# 10_DDR2.net
KiCad netlist of a schematic drawn in Altium Designer
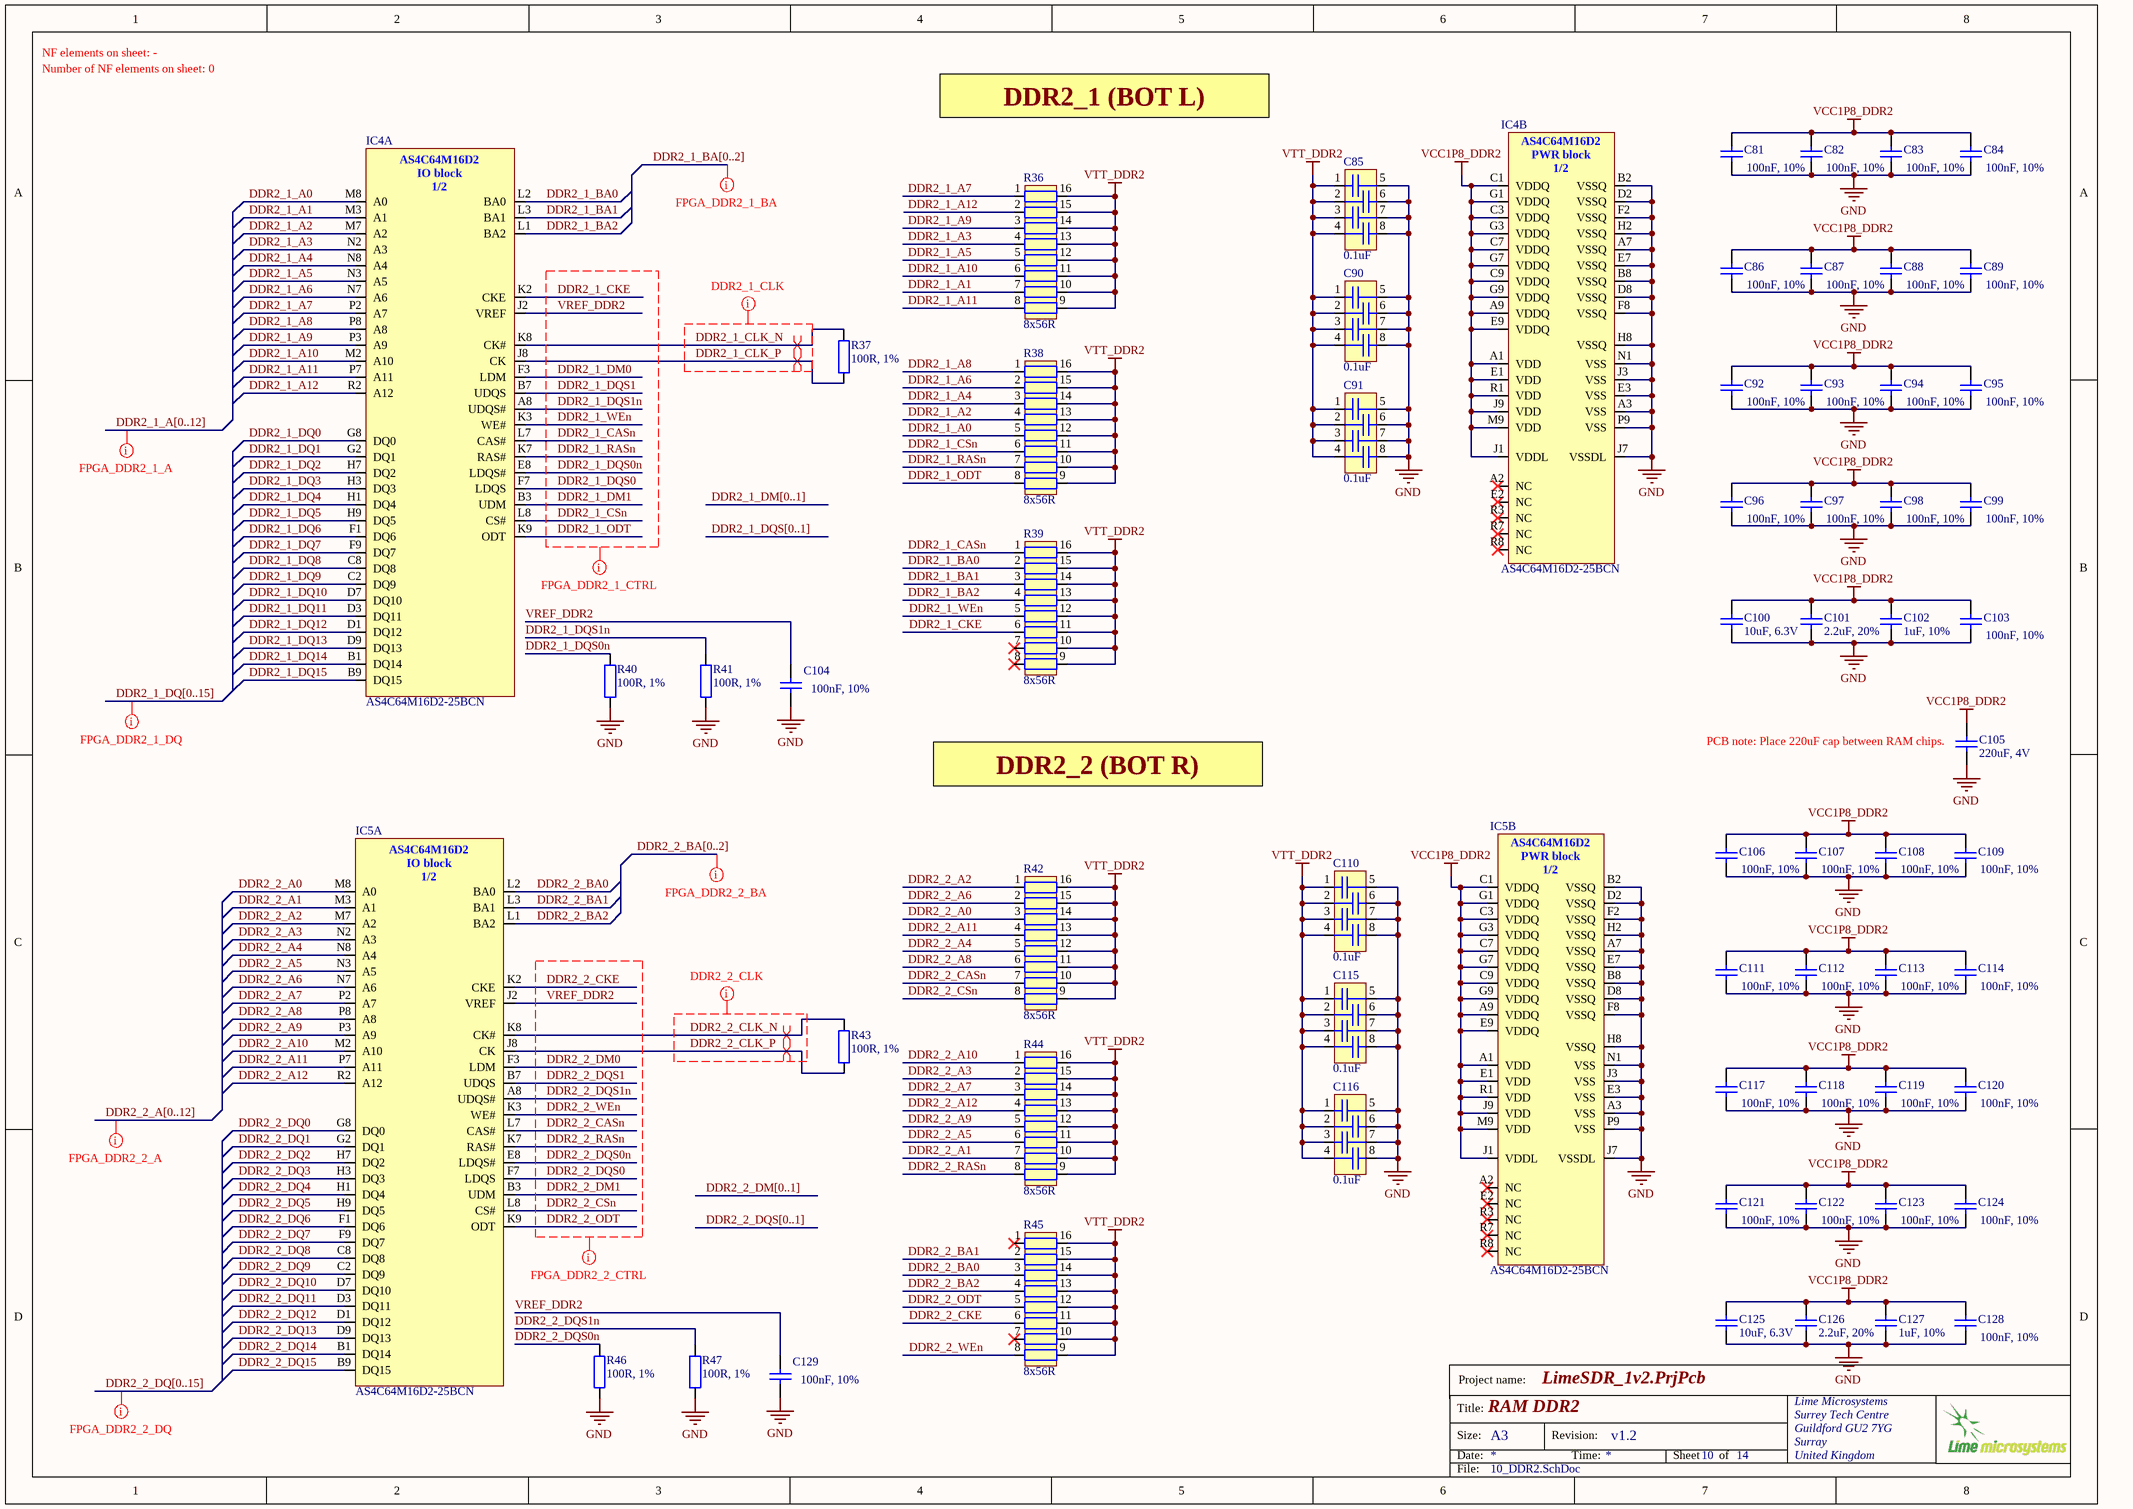
[diagram p0: 10_DDR2.SchDoc]

(export (version "E")
  (design (tool "Eeschema 10.0.6"))
  (components
    (comp (ref "C81")
      (value "100nF, 10%")
      (footprint "CAP0402")
      (fields
        (field (name "TOLERANCE") "10 %")
        (field (name "MANUFACTURER") "Murata Electronics")
        (field (name "MANUFACTURER PART NUMBER") "GRM155R71C104KA88D")
      )
      (libsource (lib "LimeFPGAboard_schLib") (part "Cap_0603"))
    )
    (comp (ref "C82")
      (value "100nF, 10%")
      (footprint "CAP0402")
      (fields
        (field (name "TOLERANCE") "10 %")
        (field (name "MANUFACTURER") "Murata Electronics")
        (field (name "MANUFACTURER PART NUMBER") "GRM155R71C104KA88D")
      )
      (libsource (lib "LimeFPGAboard_schLib") (part "Cap_0603"))
    )
    (comp (ref "C83")
      (value "100nF, 10%")
      (footprint "CAP0402")
      (fields
        (field (name "TOLERANCE") "10 %")
        (field (name "MANUFACTURER") "Murata Electronics")
        (field (name "MANUFACTURER PART NUMBER") "GRM155R71C104KA88D")
      )
      (libsource (lib "LimeFPGAboard_schLib") (part "Cap_0603"))
    )
    (comp (ref "C84")
      (value "100nF, 10%")
      (footprint "CAP0402")
      (fields
        (field (name "TOLERANCE") "10 %")
        (field (name "MANUFACTURER") "Murata Electronics")
        (field (name "MANUFACTURER PART NUMBER") "GRM155R71C104KA88D")
      )
      (libsource (lib "LimeFPGAboard_schLib") (part "Cap_0603"))
    )
    (comp (ref "C85")
      (value "0.1uF")
      (footprint "CKCA43X7R1C104M100AA")
      (fields (field (name "MANUFACTURER") "TDK") (field (name "TOLERANCE") "20 %"))
      (libsource (lib "LimeFPGAboard_schLib") (part "4X_cap_array_1206"))
    )
    (comp (ref "C86")
      (value "100nF, 10%")
      (footprint "CAP0402")
      (fields
        (field (name "TOLERANCE") "10 %")
        (field (name "MANUFACTURER") "Murata Electronics")
        (field (name "MANUFACTURER PART NUMBER") "GRM155R71C104KA88D")
      )
      (libsource (lib "LimeFPGAboard_schLib") (part "Cap_0603"))
    )
    (comp (ref "C87")
      (value "100nF, 10%")
      (footprint "CAP0402")
      (fields
        (field (name "TOLERANCE") "10 %")
        (field (name "MANUFACTURER") "Murata Electronics")
        (field (name "MANUFACTURER PART NUMBER") "GRM155R71C104KA88D")
      )
      (libsource (lib "LimeFPGAboard_schLib") (part "Cap_0603"))
    )
    (comp (ref "C88")
      (value "100nF, 10%")
      (footprint "CAP0402")
      (fields
        (field (name "TOLERANCE") "10 %")
        (field (name "MANUFACTURER") "Murata Electronics")
        (field (name "MANUFACTURER PART NUMBER") "GRM155R71C104KA88D")
      )
      (libsource (lib "LimeFPGAboard_schLib") (part "Cap_0603"))
    )
    (comp (ref "C89")
      (value "100nF, 10%")
      (footprint "CAP0402")
      (fields
        (field (name "TOLERANCE") "10 %")
        (field (name "MANUFACTURER") "Murata Electronics")
        (field (name "MANUFACTURER PART NUMBER") "GRM155R71C104KA88D")
      )
      (libsource (lib "LimeFPGAboard_schLib") (part "Cap_0603"))
    )
    (comp (ref "C90")
      (value "0.1uF")
      (footprint "CKCA43X7R1C104M100AA")
      (fields (field (name "MANUFACTURER") "TDK") (field (name "TOLERANCE") "20 %"))
      (libsource (lib "LimeFPGAboard_schLib") (part "4X_cap_array_1206"))
    )
    (comp (ref "C91")
      (value "0.1uF")
      (footprint "CKCA43X7R1C104M100AA")
      (fields (field (name "MANUFACTURER") "TDK") (field (name "TOLERANCE") "20 %"))
      (libsource (lib "LimeFPGAboard_schLib") (part "4X_cap_array_1206"))
    )
    (comp (ref "C92")
      (value "100nF, 10%")
      (footprint "CAP0402")
      (fields
        (field (name "TOLERANCE") "10 %")
        (field (name "MANUFACTURER") "Murata Electronics")
        (field (name "MANUFACTURER PART NUMBER") "GRM155R71C104KA88D")
      )
      (libsource (lib "LimeFPGAboard_schLib") (part "Cap_0603"))
    )
    (comp (ref "C93")
      (value "100nF, 10%")
      (footprint "CAP0402")
      (fields
        (field (name "TOLERANCE") "10 %")
        (field (name "MANUFACTURER") "Murata Electronics")
        (field (name "MANUFACTURER PART NUMBER") "GRM155R71C104KA88D")
      )
      (libsource (lib "LimeFPGAboard_schLib") (part "Cap_0603"))
    )
    (comp (ref "C94")
      (value "100nF, 10%")
      (footprint "CAP0402")
      (fields
        (field (name "TOLERANCE") "10 %")
        (field (name "MANUFACTURER") "Murata Electronics")
        (field (name "MANUFACTURER PART NUMBER") "GRM155R71C104KA88D")
      )
      (libsource (lib "LimeFPGAboard_schLib") (part "Cap_0603"))
    )
    (comp (ref "C95")
      (value "100nF, 10%")
      (footprint "CAP0402")
      (fields
        (field (name "TOLERANCE") "10 %")
        (field (name "MANUFACTURER") "Murata Electronics")
        (field (name "MANUFACTURER PART NUMBER") "GRM155R71C104KA88D")
      )
      (libsource (lib "LimeFPGAboard_schLib") (part "Cap_0603"))
    )
    (comp (ref "C96")
      (value "100nF, 10%")
      (footprint "CAP0402")
      (fields
        (field (name "TOLERANCE") "10 %")
        (field (name "MANUFACTURER") "Murata Electronics")
        (field (name "MANUFACTURER PART NUMBER") "GRM155R71C104KA88D")
      )
      (libsource (lib "LimeFPGAboard_schLib") (part "Cap_0603"))
    )
    (comp (ref "C97")
      (value "100nF, 10%")
      (footprint "CAP0402")
      (fields
        (field (name "TOLERANCE") "10 %")
        (field (name "MANUFACTURER") "Murata Electronics")
        (field (name "MANUFACTURER PART NUMBER") "GRM155R71C104KA88D")
      )
      (libsource (lib "LimeFPGAboard_schLib") (part "Cap_0603"))
    )
    (comp (ref "C98")
      (value "100nF, 10%")
      (footprint "CAP0402")
      (fields
        (field (name "TOLERANCE") "10 %")
        (field (name "MANUFACTURER") "Murata Electronics")
        (field (name "MANUFACTURER PART NUMBER") "GRM155R71C104KA88D")
      )
      (libsource (lib "LimeFPGAboard_schLib") (part "Cap_0603"))
    )
    (comp (ref "C99")
      (value "100nF, 10%")
      (footprint "CAP0402")
      (fields
        (field (name "TOLERANCE") "10 %")
        (field (name "MANUFACTURER") "Murata Electronics")
        (field (name "MANUFACTURER PART NUMBER") "GRM155R71C104KA88D")
      )
      (libsource (lib "LimeFPGAboard_schLib") (part "Cap_0603"))
    )
    (comp (ref "C100")
      (value "10uF, 6.3V")
      (footprint "CAP0603")
      (fields (field (name "TOLERANCE") "±20%") (field (name "MANUFACTURER") "Yageo"))
      (libsource (lib "LimeFPGAboard_schLib") (part "Cap_0603"))
    )
    (comp (ref "C101")
      (value "2.2uF, 20%")
      (footprint "CAP0402")
      (fields (field (name "MANUFACTURER") "TDK Corporation") (field (name "TOLERANCE") "±20%"))
      (libsource (lib "LimeMicroAltiumLib_schLib") (part "Cap_0402"))
    )
    (comp (ref "C102")
      (value "1uF, 10%")
      (footprint "CAP0402")
      (fields (field (name "MANUFACTURER") "TDK"))
      (libsource (lib "LimeMicroAltiumLib_schLib") (part "Cap_0402"))
    )
    (comp (ref "C103")
      (value "100nF, 10%")
      (footprint "CAP0402")
      (fields
        (field (name "TOLERANCE") "10 %")
        (field (name "MANUFACTURER") "Murata Electronics")
        (field (name "MANUFACTURER PART NUMBER") "GRM155R71C104KA88D")
      )
      (libsource (lib "LimeFPGAboard_schLib") (part "Cap_0603"))
    )
    (comp (ref "C104")
      (value "100nF, 10%")
      (footprint "CAP0402")
      (fields
        (field (name "TOLERANCE") "10 %")
        (field (name "MANUFACTURER") "Murata Electronics")
        (field (name "MANUFACTURER PART NUMBER") "GRM155R71C104KA88D")
      )
      (libsource (lib "LimeFPGAboard_schLib") (part "Cap_0603"))
    )
    (comp (ref "C105")
      (value "220uF, 4V")
      (footprint "LimeMicroAltiumLib_pcbLib:CAP1206")
      (fields
        (field (name "MANUFACTURER PART NUMBER") "GRM31CR60G227ME11L")
        (field (name "MANUFACTURER") "Murata Electronics North America")
        (field (name "TOLERANCE") "±20%")
      )
      (libsource (lib "LimeFPGAboard_schLib") (part "Cap_1206"))
    )
    (comp (ref "C106")
      (value "100nF, 10%")
      (footprint "CAP0402")
      (fields
        (field (name "TOLERANCE") "10 %")
        (field (name "MANUFACTURER") "Murata Electronics")
        (field (name "MANUFACTURER PART NUMBER") "GRM155R71C104KA88D")
      )
      (libsource (lib "LimeFPGAboard_schLib") (part "Cap_0603"))
    )
    (comp (ref "C107")
      (value "100nF, 10%")
      (footprint "CAP0402")
      (fields
        (field (name "TOLERANCE") "10 %")
        (field (name "MANUFACTURER") "Murata Electronics")
        (field (name "MANUFACTURER PART NUMBER") "GRM155R71C104KA88D")
      )
      (libsource (lib "LimeFPGAboard_schLib") (part "Cap_0603"))
    )
    (comp (ref "C108")
      (value "100nF, 10%")
      (footprint "CAP0402")
      (fields
        (field (name "TOLERANCE") "10 %")
        (field (name "MANUFACTURER") "Murata Electronics")
        (field (name "MANUFACTURER PART NUMBER") "GRM155R71C104KA88D")
      )
      (libsource (lib "LimeFPGAboard_schLib") (part "Cap_0603"))
    )
    (comp (ref "C109")
      (value "100nF, 10%")
      (footprint "CAP0402")
      (fields
        (field (name "TOLERANCE") "10 %")
        (field (name "MANUFACTURER") "Murata Electronics")
        (field (name "MANUFACTURER PART NUMBER") "GRM155R71C104KA88D")
      )
      (libsource (lib "LimeFPGAboard_schLib") (part "Cap_0603"))
    )
    (comp (ref "C110")
      (value "0.1uF")
      (footprint "CKCA43X7R1C104M100AA")
      (fields (field (name "MANUFACTURER") "TDK") (field (name "TOLERANCE") "20 %"))
      (libsource (lib "LimeFPGAboard_schLib") (part "4X_cap_array_1206"))
    )
    (comp (ref "C111")
      (value "100nF, 10%")
      (footprint "CAP0402")
      (fields
        (field (name "TOLERANCE") "10 %")
        (field (name "MANUFACTURER") "Murata Electronics")
        (field (name "MANUFACTURER PART NUMBER") "GRM155R71C104KA88D")
      )
      (libsource (lib "LimeFPGAboard_schLib") (part "Cap_0603"))
    )
    (comp (ref "C112")
      (value "100nF, 10%")
      (footprint "CAP0402")
      (fields
        (field (name "TOLERANCE") "10 %")
        (field (name "MANUFACTURER") "Murata Electronics")
        (field (name "MANUFACTURER PART NUMBER") "GRM155R71C104KA88D")
      )
      (libsource (lib "LimeFPGAboard_schLib") (part "Cap_0603"))
    )
    (comp (ref "C113")
      (value "100nF, 10%")
      (footprint "CAP0402")
      (fields
        (field (name "TOLERANCE") "10 %")
        (field (name "MANUFACTURER") "Murata Electronics")
        (field (name "MANUFACTURER PART NUMBER") "GRM155R71C104KA88D")
      )
      (libsource (lib "LimeFPGAboard_schLib") (part "Cap_0603"))
    )
    (comp (ref "C114")
      (value "100nF, 10%")
      (footprint "CAP0402")
      (fields
        (field (name "TOLERANCE") "10 %")
        (field (name "MANUFACTURER") "Murata Electronics")
        (field (name "MANUFACTURER PART NUMBER") "GRM155R71C104KA88D")
      )
      (libsource (lib "LimeFPGAboard_schLib") (part "Cap_0603"))
    )
    (comp (ref "C115")
      (value "0.1uF")
      (footprint "CKCA43X7R1C104M100AA")
      (fields (field (name "MANUFACTURER") "TDK") (field (name "TOLERANCE") "20 %"))
      (libsource (lib "LimeFPGAboard_schLib") (part "4X_cap_array_1206"))
    )
    (comp (ref "C116")
      (value "0.1uF")
      (footprint "CKCA43X7R1C104M100AA")
      (fields (field (name "MANUFACTURER") "TDK") (field (name "TOLERANCE") "20 %"))
      (libsource (lib "LimeFPGAboard_schLib") (part "4X_cap_array_1206"))
    )
    (comp (ref "C117")
      (value "100nF, 10%")
      (footprint "CAP0402")
      (fields
        (field (name "TOLERANCE") "10 %")
        (field (name "MANUFACTURER") "Murata Electronics")
        (field (name "MANUFACTURER PART NUMBER") "GRM155R71C104KA88D")
      )
      (libsource (lib "LimeFPGAboard_schLib") (part "Cap_0603"))
    )
    (comp (ref "C118")
      (value "100nF, 10%")
      (footprint "CAP0402")
      (fields
        (field (name "TOLERANCE") "10 %")
        (field (name "MANUFACTURER") "Murata Electronics")
        (field (name "MANUFACTURER PART NUMBER") "GRM155R71C104KA88D")
      )
      (libsource (lib "LimeFPGAboard_schLib") (part "Cap_0603"))
    )
    (comp (ref "C119")
      (value "100nF, 10%")
      (footprint "CAP0402")
      (fields
        (field (name "TOLERANCE") "10 %")
        (field (name "MANUFACTURER") "Murata Electronics")
        (field (name "MANUFACTURER PART NUMBER") "GRM155R71C104KA88D")
      )
      (libsource (lib "LimeFPGAboard_schLib") (part "Cap_0603"))
    )
    (comp (ref "C120")
      (value "100nF, 10%")
      (footprint "CAP0402")
      (fields
        (field (name "TOLERANCE") "10 %")
        (field (name "MANUFACTURER") "Murata Electronics")
        (field (name "MANUFACTURER PART NUMBER") "GRM155R71C104KA88D")
      )
      (libsource (lib "LimeFPGAboard_schLib") (part "Cap_0603"))
    )
    (comp (ref "C121")
      (value "100nF, 10%")
      (footprint "CAP0402")
      (fields
        (field (name "TOLERANCE") "10 %")
        (field (name "MANUFACTURER") "Murata Electronics")
        (field (name "MANUFACTURER PART NUMBER") "GRM155R71C104KA88D")
      )
      (libsource (lib "LimeFPGAboard_schLib") (part "Cap_0603"))
    )
    (comp (ref "C122")
      (value "100nF, 10%")
      (footprint "CAP0402")
      (fields
        (field (name "TOLERANCE") "10 %")
        (field (name "MANUFACTURER") "Murata Electronics")
        (field (name "MANUFACTURER PART NUMBER") "GRM155R71C104KA88D")
      )
      (libsource (lib "LimeFPGAboard_schLib") (part "Cap_0603"))
    )
    (comp (ref "C123")
      (value "100nF, 10%")
      (footprint "CAP0402")
      (fields
        (field (name "TOLERANCE") "10 %")
        (field (name "MANUFACTURER") "Murata Electronics")
        (field (name "MANUFACTURER PART NUMBER") "GRM155R71C104KA88D")
      )
      (libsource (lib "LimeFPGAboard_schLib") (part "Cap_0603"))
    )
    (comp (ref "C124")
      (value "100nF, 10%")
      (footprint "CAP0402")
      (fields
        (field (name "TOLERANCE") "10 %")
        (field (name "MANUFACTURER") "Murata Electronics")
        (field (name "MANUFACTURER PART NUMBER") "GRM155R71C104KA88D")
      )
      (libsource (lib "LimeFPGAboard_schLib") (part "Cap_0603"))
    )
    (comp (ref "C125")
      (value "10uF, 6.3V")
      (footprint "CAP0603")
      (fields (field (name "TOLERANCE") "±20%") (field (name "MANUFACTURER") "Yageo"))
      (libsource (lib "LimeFPGAboard_schLib") (part "Cap_0603"))
    )
    (comp (ref "C126")
      (value "2.2uF, 20%")
      (footprint "CAP0402")
      (fields (field (name "MANUFACTURER") "TDK Corporation") (field (name "TOLERANCE") "±20%"))
      (libsource (lib "LimeMicroAltiumLib_schLib") (part "Cap_0402"))
    )
    (comp (ref "C127")
      (value "1uF, 10%")
      (footprint "CAP0402")
      (fields (field (name "MANUFACTURER") "TDK"))
      (libsource (lib "LimeMicroAltiumLib_schLib") (part "Cap_0402"))
    )
    (comp (ref "C128")
      (value "100nF, 10%")
      (footprint "CAP0402")
      (fields
        (field (name "TOLERANCE") "10 %")
        (field (name "MANUFACTURER") "Murata Electronics")
        (field (name "MANUFACTURER PART NUMBER") "GRM155R71C104KA88D")
      )
      (libsource (lib "LimeFPGAboard_schLib") (part "Cap_0603"))
    )
    (comp (ref "C129")
      (value "100nF, 10%")
      (footprint "CAP0402")
      (fields
        (field (name "TOLERANCE") "10 %")
        (field (name "MANUFACTURER") "Murata Electronics")
        (field (name "MANUFACTURER PART NUMBER") "GRM155R71C104KA88D")
      )
      (libsource (lib "LimeFPGAboard_schLib") (part "Cap_0603"))
    )
    (comp (ref "IC4")
      (value "AS4C64M16D2-25BCN")
      (footprint "AS4C64M16D2")
      (fields (field (name "MANUFACTURER") "Alliance Memory, Inc."))
      (libsource (lib "LimeMicroAltiumLib_schLib") (part "AS4C64M16D2-25BCN"))
    )
    (comp (ref "IC5")
      (value "AS4C64M16D2-25BCN")
      (footprint "AS4C64M16D2")
      (fields (field (name "MANUFACTURER") "Alliance Memory, Inc."))
      (libsource (lib "LimeMicroAltiumLib_schLib") (part "AS4C64M16D2-25BCN"))
    )
    (comp (ref "R36")
      (value "8x56R")
      (footprint "EXB2HV")
      (fields (field (name "MANUFACTURER") "PANASONIC ELECTRONIC COMPONENTS"))
      (libsource (lib "LimeFPGAboard_schLib") (part "8X_resistor_array_0402"))
    )
    (comp (ref "R37")
      (value "100R, 1%")
      (footprint "RES0402")
      (fields (field (name "TOLERANCE") "±1%"))
      (libsource (lib "LimeFPGAboard_schLib") (part "Res_0402"))
    )
    (comp (ref "R38")
      (value "8x56R")
      (footprint "EXB2HV")
      (fields (field (name "MANUFACTURER") "PANASONIC ELECTRONIC COMPONENTS"))
      (libsource (lib "LimeFPGAboard_schLib") (part "8X_resistor_array_0402"))
    )
    (comp (ref "R39")
      (value "8x56R")
      (footprint "EXB2HV")
      (fields (field (name "MANUFACTURER") "PANASONIC ELECTRONIC COMPONENTS"))
      (libsource (lib "LimeFPGAboard_schLib") (part "8X_resistor_array_0402"))
    )
    (comp (ref "R40")
      (value "100R, 1%")
      (footprint "RES0402")
      (fields (field (name "TOLERANCE") "±1%"))
      (libsource (lib "LimeFPGAboard_schLib") (part "Res_0402"))
    )
    (comp (ref "R41")
      (value "100R, 1%")
      (footprint "RES0402")
      (fields (field (name "TOLERANCE") "±1%"))
      (libsource (lib "LimeFPGAboard_schLib") (part "Res_0402"))
    )
    (comp (ref "R42")
      (value "8x56R")
      (footprint "EXB2HV")
      (fields (field (name "MANUFACTURER") "PANASONIC ELECTRONIC COMPONENTS"))
      (libsource (lib "LimeFPGAboard_schLib") (part "8X_resistor_array_0402"))
    )
    (comp (ref "R43")
      (value "100R, 1%")
      (footprint "RES0402")
      (fields (field (name "TOLERANCE") "±1%"))
      (libsource (lib "LimeFPGAboard_schLib") (part "Res_0402"))
    )
    (comp (ref "R44")
      (value "8x56R")
      (footprint "EXB2HV")
      (fields (field (name "MANUFACTURER") "PANASONIC ELECTRONIC COMPONENTS"))
      (libsource (lib "LimeFPGAboard_schLib") (part "8X_resistor_array_0402"))
    )
    (comp (ref "R45")
      (value "8x56R")
      (footprint "EXB2HV")
      (fields (field (name "MANUFACTURER") "PANASONIC ELECTRONIC COMPONENTS"))
      (libsource (lib "LimeFPGAboard_schLib") (part "8X_resistor_array_0402"))
    )
    (comp (ref "R46")
      (value "100R, 1%")
      (footprint "RES0402")
      (fields (field (name "TOLERANCE") "±1%"))
      (libsource (lib "LimeFPGAboard_schLib") (part "Res_0402"))
    )
    (comp (ref "R47")
      (value "100R, 1%")
      (footprint "RES0402")
      (fields (field (name "TOLERANCE") "±1%"))
      (libsource (lib "LimeFPGAboard_schLib") (part "Res_0402"))
    )
  )
  (nets
    (net (code "1") (name "/DDR2_1_A0") (class "Default")
      (node (ref "IC4") (pin "M8") (pinfunction "A0_M8") (pintype "passive"))
      (node (ref "R38") (pin "5") (pinfunction "5_5") (pintype "passive"))
    )
    (net (code "2") (name "/DDR2_1_A1") (class "Default")
      (node (ref "IC4") (pin "M3") (pinfunction "A1_M3") (pintype "passive"))
      (node (ref "R36") (pin "7") (pinfunction "7_7") (pintype "passive"))
    )
    (net (code "3") (name "/DDR2_1_A2") (class "Default")
      (node (ref "IC4") (pin "M7") (pinfunction "A2_M7") (pintype "passive"))
      (node (ref "R38") (pin "4") (pinfunction "4_4") (pintype "passive"))
    )
    (net (code "4") (name "/DDR2_1_A3") (class "Default")
      (node (ref "IC4") (pin "N2") (pinfunction "A3_N2") (pintype "passive"))
      (node (ref "R36") (pin "4") (pinfunction "4_4") (pintype "passive"))
    )
    (net (code "5") (name "/DDR2_1_A4") (class "Default")
      (node (ref "IC4") (pin "N8") (pinfunction "A4_N8") (pintype "passive"))
      (node (ref "R38") (pin "3") (pinfunction "3_3") (pintype "passive"))
    )
    (net (code "6") (name "/DDR2_1_A5") (class "Default")
      (node (ref "IC4") (pin "N3") (pinfunction "A5_N3") (pintype "passive"))
      (node (ref "R36") (pin "5") (pinfunction "5_5") (pintype "passive"))
    )
    (net (code "7") (name "/DDR2_1_A6") (class "Default")
      (node (ref "IC4") (pin "N7") (pinfunction "A6_N7") (pintype "passive"))
      (node (ref "R38") (pin "2") (pinfunction "2_2") (pintype "passive"))
    )
    (net (code "8") (name "/DDR2_1_A7") (class "Default")
      (node (ref "IC4") (pin "P2") (pinfunction "A7_P2") (pintype "passive"))
      (node (ref "R36") (pin "1") (pinfunction "1_1") (pintype "passive"))
    )
    (net (code "9") (name "/DDR2_1_A8") (class "Default")
      (node (ref "IC4") (pin "P8") (pinfunction "A8_P8") (pintype "passive"))
      (node (ref "R38") (pin "1") (pinfunction "1_1") (pintype "passive"))
    )
    (net (code "10") (name "/DDR2_1_A9") (class "Default")
      (node (ref "IC4") (pin "P3") (pinfunction "A9_P3") (pintype "passive"))
      (node (ref "R36") (pin "3") (pinfunction "3_3") (pintype "passive"))
    )
    (net (code "11") (name "/DDR2_1_A10") (class "Default")
      (node (ref "IC4") (pin "M2") (pinfunction "A10_M2") (pintype "passive"))
      (node (ref "R36") (pin "6") (pinfunction "6_6") (pintype "passive"))
    )
    (net (code "12") (name "/DDR2_1_A11") (class "Default")
      (node (ref "IC4") (pin "P7") (pinfunction "A11_P7") (pintype "passive"))
      (node (ref "R36") (pin "8") (pinfunction "8_8") (pintype "passive"))
    )
    (net (code "13") (name "/DDR2_1_A12") (class "Default")
      (node (ref "IC4") (pin "R2") (pinfunction "A12_R2") (pintype "passive"))
      (node (ref "R36") (pin "2") (pinfunction "2_2") (pintype "passive"))
    )
    (net (code "15") (name "/DDR2_1_BA0") (class "Default")
      (node (ref "IC4") (pin "L2") (pinfunction "BA0_L2") (pintype "passive"))
      (node (ref "R39") (pin "2") (pinfunction "2_2") (pintype "passive"))
    )
    (net (code "16") (name "/DDR2_1_BA1") (class "Default")
      (node (ref "IC4") (pin "L3") (pinfunction "BA1_L3") (pintype "passive"))
      (node (ref "R39") (pin "3") (pinfunction "3_3") (pintype "passive"))
    )
    (net (code "17") (name "/DDR2_1_BA2") (class "Default")
      (node (ref "IC4") (pin "L1") (pinfunction "BA2_L1") (pintype "passive"))
      (node (ref "R39") (pin "4") (pinfunction "4_4") (pintype "passive"))
    )
    (net (code "19") (name "/DDR2_1_CASn") (class "Default")
      (node (ref "IC4") (pin "L7") (pinfunction "CAS#_L7") (pintype "passive"))
      (node (ref "R39") (pin "1") (pinfunction "1_1") (pintype "passive"))
    )
    (net (code "20") (name "/DDR2_1_CKE") (class "Default")
      (node (ref "IC4") (pin "K2") (pinfunction "CKE_K2") (pintype "passive"))
      (node (ref "R39") (pin "6") (pinfunction "6_6") (pintype "passive"))
    )
    (net (code "21") (name "/DDR2_1_CLK_N") (class "Default")
      (node (ref "IC4") (pin "K8") (pinfunction "CK#_K8") (pintype "passive"))
      (node (ref "R37") (pin "2") (pinfunction "2_2") (pintype "passive"))
    )
    (net (code "22") (name "/DDR2_1_CLK_P") (class "Default")
      (node (ref "IC4") (pin "J8") (pinfunction "CK_J8") (pintype "passive"))
      (node (ref "R37") (pin "1") (pinfunction "1_1") (pintype "passive"))
    )
    (net (code "23") (name "/DDR2_1_CSn") (class "Default")
      (node (ref "IC4") (pin "L8") (pinfunction "CS#_L8") (pintype "passive"))
      (node (ref "R38") (pin "6") (pinfunction "6_6") (pintype "passive"))
    )
    (net (code "24") (name "/DDR2_1_DM0") (class "Default")
      (node (ref "IC4") (pin "F3") (pinfunction "LDM_F3") (pintype "passive"))
    )
    (net (code "25") (name "/DDR2_1_DM1") (class "Default")
      (node (ref "IC4") (pin "B3") (pinfunction "UDM_B3") (pintype "passive"))
    )
    (net (code "27") (name "/DDR2_1_DQ0") (class "Default")
      (node (ref "IC4") (pin "G8") (pinfunction "DQ0_G8") (pintype "passive"))
    )
    (net (code "28") (name "/DDR2_1_DQ1") (class "Default")
      (node (ref "IC4") (pin "G2") (pinfunction "DQ1_G2") (pintype "passive"))
    )
    (net (code "29") (name "/DDR2_1_DQ2") (class "Default")
      (node (ref "IC4") (pin "H7") (pinfunction "DQ2_H7") (pintype "passive"))
    )
    (net (code "30") (name "/DDR2_1_DQ3") (class "Default")
      (node (ref "IC4") (pin "H3") (pinfunction "DQ3_H3") (pintype "passive"))
    )
    (net (code "31") (name "/DDR2_1_DQ4") (class "Default")
      (node (ref "IC4") (pin "H1") (pinfunction "DQ4_H1") (pintype "passive"))
    )
    (net (code "32") (name "/DDR2_1_DQ5") (class "Default")
      (node (ref "IC4") (pin "H9") (pinfunction "DQ5_H9") (pintype "passive"))
    )
    (net (code "33") (name "/DDR2_1_DQ6") (class "Default")
      (node (ref "IC4") (pin "F1") (pinfunction "DQ6_F1") (pintype "passive"))
    )
    (net (code "34") (name "/DDR2_1_DQ7") (class "Default")
      (node (ref "IC4") (pin "F9") (pinfunction "DQ7_F9") (pintype "passive"))
    )
    (net (code "35") (name "/DDR2_1_DQ8") (class "Default")
      (node (ref "IC4") (pin "C8") (pinfunction "DQ8_C8") (pintype "passive"))
    )
    (net (code "36") (name "/DDR2_1_DQ9") (class "Default")
      (node (ref "IC4") (pin "C2") (pinfunction "DQ9_C2") (pintype "passive"))
    )
    (net (code "37") (name "/DDR2_1_DQ10") (class "Default")
      (node (ref "IC4") (pin "D7") (pinfunction "DQ10_D7") (pintype "passive"))
    )
    (net (code "38") (name "/DDR2_1_DQ11") (class "Default")
      (node (ref "IC4") (pin "D3") (pinfunction "DQ11_D3") (pintype "passive"))
    )
    (net (code "39") (name "/DDR2_1_DQ12") (class "Default")
      (node (ref "IC4") (pin "D1") (pinfunction "DQ12_D1") (pintype "passive"))
    )
    (net (code "40") (name "/DDR2_1_DQ13") (class "Default")
      (node (ref "IC4") (pin "D9") (pinfunction "DQ13_D9") (pintype "passive"))
    )
    (net (code "41") (name "/DDR2_1_DQ14") (class "Default")
      (node (ref "IC4") (pin "B1") (pinfunction "DQ14_B1") (pintype "passive"))
    )
    (net (code "42") (name "/DDR2_1_DQ15") (class "Default")
      (node (ref "IC4") (pin "B9") (pinfunction "DQ15_B9") (pintype "passive"))
    )
    (net (code "43") (name "/DDR2_1_DQS0") (class "Default")
      (node (ref "IC4") (pin "F7") (pinfunction "LDQS_F7") (pintype "passive"))
    )
    (net (code "44") (name "/DDR2_1_DQS0n") (class "Default")
      (node (ref "IC4") (pin "E8") (pinfunction "LDQS#_E8") (pintype "passive"))
      (node (ref "R40") (pin "2") (pinfunction "2_2") (pintype "passive"))
    )
    (net (code "45") (name "/DDR2_1_DQS1") (class "Default")
      (node (ref "IC4") (pin "B7") (pinfunction "UDQS_B7") (pintype "passive"))
    )
    (net (code "46") (name "/DDR2_1_DQS1n") (class "Default")
      (node (ref "IC4") (pin "A8") (pinfunction "UDQS#_A8") (pintype "passive"))
      (node (ref "R41") (pin "2") (pinfunction "2_2") (pintype "passive"))
    )
    (net (code "49") (name "/DDR2_1_ODT") (class "Default")
      (node (ref "IC4") (pin "K9") (pinfunction "ODT_K9") (pintype "passive"))
      (node (ref "R38") (pin "8") (pinfunction "8_8") (pintype "passive"))
    )
    (net (code "50") (name "/DDR2_1_RASn") (class "Default")
      (node (ref "IC4") (pin "K7") (pinfunction "RAS#_K7") (pintype "passive"))
      (node (ref "R38") (pin "7") (pinfunction "7_7") (pintype "passive"))
    )
    (net (code "51") (name "/DDR2_1_WEn") (class "Default")
      (node (ref "IC4") (pin "K3") (pinfunction "WE#_K3") (pintype "passive"))
      (node (ref "R39") (pin "5") (pinfunction "5_5") (pintype "passive"))
    )
    (net (code "52") (name "/DDR2_2_A0") (class "Default")
      (node (ref "IC5") (pin "M8") (pinfunction "A0_M8") (pintype "passive"))
      (node (ref "R42") (pin "3") (pinfunction "3_3") (pintype "passive"))
    )
    (net (code "53") (name "/DDR2_2_A1") (class "Default")
      (node (ref "IC5") (pin "M3") (pinfunction "A1_M3") (pintype "passive"))
      (node (ref "R44") (pin "7") (pinfunction "7_7") (pintype "passive"))
    )
    (net (code "54") (name "/DDR2_2_A2") (class "Default")
      (node (ref "IC5") (pin "M7") (pinfunction "A2_M7") (pintype "passive"))
      (node (ref "R42") (pin "1") (pinfunction "1_1") (pintype "passive"))
    )
    (net (code "55") (name "/DDR2_2_A3") (class "Default")
      (node (ref "IC5") (pin "N2") (pinfunction "A3_N2") (pintype "passive"))
      (node (ref "R44") (pin "2") (pinfunction "2_2") (pintype "passive"))
    )
    (net (code "56") (name "/DDR2_2_A4") (class "Default")
      (node (ref "IC5") (pin "N8") (pinfunction "A4_N8") (pintype "passive"))
      (node (ref "R42") (pin "5") (pinfunction "5_5") (pintype "passive"))
    )
    (net (code "57") (name "/DDR2_2_A5") (class "Default")
      (node (ref "IC5") (pin "N3") (pinfunction "A5_N3") (pintype "passive"))
      (node (ref "R44") (pin "6") (pinfunction "6_6") (pintype "passive"))
    )
    (net (code "58") (name "/DDR2_2_A6") (class "Default")
      (node (ref "IC5") (pin "N7") (pinfunction "A6_N7") (pintype "passive"))
      (node (ref "R42") (pin "2") (pinfunction "2_2") (pintype "passive"))
    )
    (net (code "59") (name "/DDR2_2_A7") (class "Default")
      (node (ref "IC5") (pin "P2") (pinfunction "A7_P2") (pintype "passive"))
      (node (ref "R44") (pin "3") (pinfunction "3_3") (pintype "passive"))
    )
    (net (code "60") (name "/DDR2_2_A8") (class "Default")
      (node (ref "IC5") (pin "P8") (pinfunction "A8_P8") (pintype "passive"))
      (node (ref "R42") (pin "6") (pinfunction "6_6") (pintype "passive"))
    )
    (net (code "61") (name "/DDR2_2_A9") (class "Default")
      (node (ref "IC5") (pin "P3") (pinfunction "A9_P3") (pintype "passive"))
      (node (ref "R44") (pin "5") (pinfunction "5_5") (pintype "passive"))
    )
    (net (code "62") (name "/DDR2_2_A10") (class "Default")
      (node (ref "IC5") (pin "M2") (pinfunction "A10_M2") (pintype "passive"))
      (node (ref "R44") (pin "1") (pinfunction "1_1") (pintype "passive"))
    )
    (net (code "63") (name "/DDR2_2_A11") (class "Default")
      (node (ref "IC5") (pin "P7") (pinfunction "A11_P7") (pintype "passive"))
      (node (ref "R42") (pin "4") (pinfunction "4_4") (pintype "passive"))
    )
    (net (code "64") (name "/DDR2_2_A12") (class "Default")
      (node (ref "IC5") (pin "R2") (pinfunction "A12_R2") (pintype "passive"))
      (node (ref "R44") (pin "4") (pinfunction "4_4") (pintype "passive"))
    )
    (net (code "66") (name "/DDR2_2_BA0") (class "Default")
      (node (ref "IC5") (pin "L2") (pinfunction "BA0_L2") (pintype "passive"))
      (node (ref "R45") (pin "3") (pinfunction "3_3") (pintype "passive"))
    )
    (net (code "67") (name "/DDR2_2_BA1") (class "Default")
      (node (ref "IC5") (pin "L3") (pinfunction "BA1_L3") (pintype "passive"))
      (node (ref "R45") (pin "2") (pinfunction "2_2") (pintype "passive"))
    )
    (net (code "68") (name "/DDR2_2_BA2") (class "Default")
      (node (ref "IC5") (pin "L1") (pinfunction "BA2_L1") (pintype "passive"))
      (node (ref "R45") (pin "4") (pinfunction "4_4") (pintype "passive"))
    )
    (net (code "70") (name "/DDR2_2_CASn") (class "Default")
      (node (ref "IC5") (pin "L7") (pinfunction "CAS#_L7") (pintype "passive"))
      (node (ref "R42") (pin "7") (pinfunction "7_7") (pintype "passive"))
    )
    (net (code "71") (name "/DDR2_2_CKE") (class "Default")
      (node (ref "IC5") (pin "K2") (pinfunction "CKE_K2") (pintype "passive"))
      (node (ref "R45") (pin "6") (pinfunction "6_6") (pintype "passive"))
    )
    (net (code "72") (name "/DDR2_2_CLK_N") (class "Default")
      (node (ref "IC5") (pin "K8") (pinfunction "CK#_K8") (pintype "passive"))
      (node (ref "R43") (pin "2") (pinfunction "2_2") (pintype "passive"))
    )
    (net (code "73") (name "/DDR2_2_CLK_P") (class "Default")
      (node (ref "IC5") (pin "J8") (pinfunction "CK_J8") (pintype "passive"))
      (node (ref "R43") (pin "1") (pinfunction "1_1") (pintype "passive"))
    )
    (net (code "74") (name "/DDR2_2_CSn") (class "Default")
      (node (ref "IC5") (pin "L8") (pinfunction "CS#_L8") (pintype "passive"))
      (node (ref "R42") (pin "8") (pinfunction "8_8") (pintype "passive"))
    )
    (net (code "75") (name "/DDR2_2_DM0") (class "Default")
      (node (ref "IC5") (pin "F3") (pinfunction "LDM_F3") (pintype "passive"))
    )
    (net (code "76") (name "/DDR2_2_DM1") (class "Default")
      (node (ref "IC5") (pin "B3") (pinfunction "UDM_B3") (pintype "passive"))
    )
    (net (code "78") (name "/DDR2_2_DQ0") (class "Default")
      (node (ref "IC5") (pin "G8") (pinfunction "DQ0_G8") (pintype "passive"))
    )
    (net (code "79") (name "/DDR2_2_DQ1") (class "Default")
      (node (ref "IC5") (pin "G2") (pinfunction "DQ1_G2") (pintype "passive"))
    )
    (net (code "80") (name "/DDR2_2_DQ2") (class "Default")
      (node (ref "IC5") (pin "H7") (pinfunction "DQ2_H7") (pintype "passive"))
    )
    (net (code "81") (name "/DDR2_2_DQ3") (class "Default")
      (node (ref "IC5") (pin "H3") (pinfunction "DQ3_H3") (pintype "passive"))
    )
    (net (code "82") (name "/DDR2_2_DQ4") (class "Default")
      (node (ref "IC5") (pin "H1") (pinfunction "DQ4_H1") (pintype "passive"))
    )
    (net (code "83") (name "/DDR2_2_DQ5") (class "Default")
      (node (ref "IC5") (pin "H9") (pinfunction "DQ5_H9") (pintype "passive"))
    )
    (net (code "84") (name "/DDR2_2_DQ6") (class "Default")
      (node (ref "IC5") (pin "F1") (pinfunction "DQ6_F1") (pintype "passive"))
    )
    (net (code "85") (name "/DDR2_2_DQ7") (class "Default")
      (node (ref "IC5") (pin "F9") (pinfunction "DQ7_F9") (pintype "passive"))
    )
    (net (code "86") (name "/DDR2_2_DQ8") (class "Default")
      (node (ref "IC5") (pin "C8") (pinfunction "DQ8_C8") (pintype "passive"))
    )
    (net (code "87") (name "/DDR2_2_DQ9") (class "Default")
      (node (ref "IC5") (pin "C2") (pinfunction "DQ9_C2") (pintype "passive"))
    )
    (net (code "88") (name "/DDR2_2_DQ10") (class "Default")
      (node (ref "IC5") (pin "D7") (pinfunction "DQ10_D7") (pintype "passive"))
    )
    (net (code "89") (name "/DDR2_2_DQ11") (class "Default")
      (node (ref "IC5") (pin "D3") (pinfunction "DQ11_D3") (pintype "passive"))
    )
    (net (code "90") (name "/DDR2_2_DQ12") (class "Default")
      (node (ref "IC5") (pin "D1") (pinfunction "DQ12_D1") (pintype "passive"))
    )
    (net (code "91") (name "/DDR2_2_DQ13") (class "Default")
      (node (ref "IC5") (pin "D9") (pinfunction "DQ13_D9") (pintype "passive"))
    )
    (net (code "92") (name "/DDR2_2_DQ14") (class "Default")
      (node (ref "IC5") (pin "B1") (pinfunction "DQ14_B1") (pintype "passive"))
    )
    (net (code "93") (name "/DDR2_2_DQ15") (class "Default")
      (node (ref "IC5") (pin "B9") (pinfunction "DQ15_B9") (pintype "passive"))
    )
    (net (code "94") (name "/DDR2_2_DQS0") (class "Default")
      (node (ref "IC5") (pin "F7") (pinfunction "LDQS_F7") (pintype "passive"))
    )
    (net (code "95") (name "/DDR2_2_DQS0n") (class "Default")
      (node (ref "IC5") (pin "E8") (pinfunction "LDQS#_E8") (pintype "passive"))
      (node (ref "R46") (pin "2") (pinfunction "2_2") (pintype "passive"))
    )
    (net (code "96") (name "/DDR2_2_DQS1") (class "Default")
      (node (ref "IC5") (pin "B7") (pinfunction "UDQS_B7") (pintype "passive"))
    )
    (net (code "97") (name "/DDR2_2_DQS1n") (class "Default")
      (node (ref "IC5") (pin "A8") (pinfunction "UDQS#_A8") (pintype "passive"))
      (node (ref "R47") (pin "2") (pinfunction "2_2") (pintype "passive"))
    )
    (net (code "100") (name "/DDR2_2_ODT") (class "Default")
      (node (ref "IC5") (pin "K9") (pinfunction "ODT_K9") (pintype "passive"))
      (node (ref "R45") (pin "5") (pinfunction "5_5") (pintype "passive"))
    )
    (net (code "101") (name "/DDR2_2_RASn") (class "Default")
      (node (ref "IC5") (pin "K7") (pinfunction "RAS#_K7") (pintype "passive"))
      (node (ref "R44") (pin "8") (pinfunction "8_8") (pintype "passive"))
    )
    (net (code "102") (name "/DDR2_2_WEn") (class "Default")
      (node (ref "IC5") (pin "K3") (pinfunction "WE#_K3") (pintype "passive"))
      (node (ref "R45") (pin "8") (pinfunction "8_8") (pintype "passive"))
    )
    (net (code "103") (name "/VREF_DDR2") (class "Default")
      (node (ref "C104") (pin "1") (pinfunction "1_1") (pintype "passive"))
      (node (ref "C129") (pin "1") (pinfunction "1_1") (pintype "passive"))
      (node (ref "IC4") (pin "J2") (pinfunction "VREF_J2") (pintype "passive"))
      (node (ref "IC5") (pin "J2") (pinfunction "VREF_J2") (pintype "passive"))
    )
    (net (code "104") (name "GND") (class "Default")
      (node (ref "C100") (pin "1") (pinfunction "1_1") (pintype "passive"))
      (node (ref "C101") (pin "1") (pinfunction "1_1") (pintype "passive"))
      (node (ref "C102") (pin "1") (pinfunction "1_1") (pintype "passive"))
      (node (ref "C103") (pin "2") (pinfunction "2_2") (pintype "passive"))
      (node (ref "C104") (pin "2") (pinfunction "2_2") (pintype "passive"))
      (node (ref "C105") (pin "1") (pinfunction "1_1") (pintype "passive"))
      (node (ref "C106") (pin "2") (pinfunction "2_2") (pintype "passive"))
      (node (ref "C107") (pin "2") (pinfunction "2_2") (pintype "passive"))
      (node (ref "C108") (pin "2") (pinfunction "2_2") (pintype "passive"))
      (node (ref "C109") (pin "2") (pinfunction "2_2") (pintype "passive"))
      (node (ref "C110") (pin "5") (pinfunction "5_5") (pintype "passive"))
      (node (ref "C110") (pin "6") (pinfunction "6_6") (pintype "passive"))
      (node (ref "C110") (pin "7") (pinfunction "7_7") (pintype "passive"))
      (node (ref "C110") (pin "8") (pinfunction "8_8") (pintype "passive"))
      (node (ref "C111") (pin "2") (pinfunction "2_2") (pintype "passive"))
      (node (ref "C112") (pin "2") (pinfunction "2_2") (pintype "passive"))
      (node (ref "C113") (pin "2") (pinfunction "2_2") (pintype "passive"))
      (node (ref "C114") (pin "2") (pinfunction "2_2") (pintype "passive"))
      (node (ref "C115") (pin "5") (pinfunction "5_5") (pintype "passive"))
      (node (ref "C115") (pin "6") (pinfunction "6_6") (pintype "passive"))
      (node (ref "C115") (pin "7") (pinfunction "7_7") (pintype "passive"))
      (node (ref "C115") (pin "8") (pinfunction "8_8") (pintype "passive"))
      (node (ref "C116") (pin "5") (pinfunction "5_5") (pintype "passive"))
      (node (ref "C116") (pin "6") (pinfunction "6_6") (pintype "passive"))
      (node (ref "C116") (pin "7") (pinfunction "7_7") (pintype "passive"))
      (node (ref "C116") (pin "8") (pinfunction "8_8") (pintype "passive"))
      (node (ref "C117") (pin "2") (pinfunction "2_2") (pintype "passive"))
      (node (ref "C118") (pin "2") (pinfunction "2_2") (pintype "passive"))
      (node (ref "C119") (pin "2") (pinfunction "2_2") (pintype "passive"))
      (node (ref "C120") (pin "2") (pinfunction "2_2") (pintype "passive"))
      (node (ref "C121") (pin "2") (pinfunction "2_2") (pintype "passive"))
      (node (ref "C122") (pin "2") (pinfunction "2_2") (pintype "passive"))
      (node (ref "C123") (pin "2") (pinfunction "2_2") (pintype "passive"))
      (node (ref "C124") (pin "2") (pinfunction "2_2") (pintype "passive"))
      (node (ref "C125") (pin "1") (pinfunction "1_1") (pintype "passive"))
      (node (ref "C126") (pin "1") (pinfunction "1_1") (pintype "passive"))
      (node (ref "C127") (pin "1") (pinfunction "1_1") (pintype "passive"))
      (node (ref "C128") (pin "2") (pinfunction "2_2") (pintype "passive"))
      (node (ref "C129") (pin "2") (pinfunction "2_2") (pintype "passive"))
      (node (ref "C81") (pin "2") (pinfunction "2_2") (pintype "passive"))
      (node (ref "C82") (pin "2") (pinfunction "2_2") (pintype "passive"))
      (node (ref "C83") (pin "2") (pinfunction "2_2") (pintype "passive"))
      (node (ref "C84") (pin "2") (pinfunction "2_2") (pintype "passive"))
      (node (ref "C85") (pin "5") (pinfunction "5_5") (pintype "passive"))
      (node (ref "C85") (pin "6") (pinfunction "6_6") (pintype "passive"))
      (node (ref "C85") (pin "7") (pinfunction "7_7") (pintype "passive"))
      (node (ref "C85") (pin "8") (pinfunction "8_8") (pintype "passive"))
      (node (ref "C86") (pin "2") (pinfunction "2_2") (pintype "passive"))
      (node (ref "C87") (pin "2") (pinfunction "2_2") (pintype "passive"))
      (node (ref "C88") (pin "2") (pinfunction "2_2") (pintype "passive"))
      (node (ref "C89") (pin "2") (pinfunction "2_2") (pintype "passive"))
      (node (ref "C90") (pin "5") (pinfunction "5_5") (pintype "passive"))
      (node (ref "C90") (pin "6") (pinfunction "6_6") (pintype "passive"))
      (node (ref "C90") (pin "7") (pinfunction "7_7") (pintype "passive"))
      (node (ref "C90") (pin "8") (pinfunction "8_8") (pintype "passive"))
      (node (ref "C91") (pin "5") (pinfunction "5_5") (pintype "passive"))
      (node (ref "C91") (pin "6") (pinfunction "6_6") (pintype "passive"))
      (node (ref "C91") (pin "7") (pinfunction "7_7") (pintype "passive"))
      (node (ref "C91") (pin "8") (pinfunction "8_8") (pintype "passive"))
      (node (ref "C92") (pin "2") (pinfunction "2_2") (pintype "passive"))
      (node (ref "C93") (pin "2") (pinfunction "2_2") (pintype "passive"))
      (node (ref "C94") (pin "2") (pinfunction "2_2") (pintype "passive"))
      (node (ref "C95") (pin "2") (pinfunction "2_2") (pintype "passive"))
      (node (ref "C96") (pin "2") (pinfunction "2_2") (pintype "passive"))
      (node (ref "C97") (pin "2") (pinfunction "2_2") (pintype "passive"))
      (node (ref "C98") (pin "2") (pinfunction "2_2") (pintype "passive"))
      (node (ref "C99") (pin "2") (pinfunction "2_2") (pintype "passive"))
      (node (ref "IC4") (pin "A3") (pinfunction "VSS_A3") (pintype "power_in"))
      (node (ref "IC4") (pin "A7") (pinfunction "VSSQ_A7") (pintype "power_in"))
      (node (ref "IC4") (pin "B2") (pinfunction "VSSQ_B2") (pintype "power_in"))
      (node (ref "IC4") (pin "B8") (pinfunction "VSSQ_B8") (pintype "power_in"))
      (node (ref "IC4") (pin "D2") (pinfunction "VSSQ_D2") (pintype "power_in"))
      (node (ref "IC4") (pin "D8") (pinfunction "VSSQ_D8") (pintype "power_in"))
      (node (ref "IC4") (pin "E3") (pinfunction "VSS_E3") (pintype "power_in"))
      (node (ref "IC4") (pin "E7") (pinfunction "VSSQ_E7") (pintype "power_in"))
      (node (ref "IC4") (pin "F2") (pinfunction "VSSQ_F2") (pintype "power_in"))
      (node (ref "IC4") (pin "F8") (pinfunction "VSSQ_F8") (pintype "power_in"))
      (node (ref "IC4") (pin "H2") (pinfunction "VSSQ_H2") (pintype "power_in"))
      (node (ref "IC4") (pin "H8") (pinfunction "VSSQ_H8") (pintype "power_in"))
      (node (ref "IC4") (pin "J3") (pinfunction "VSS_J3") (pintype "power_in"))
      (node (ref "IC4") (pin "J7") (pinfunction "VSSDL_J7") (pintype "power_in"))
      (node (ref "IC4") (pin "N1") (pinfunction "VSS_N1") (pintype "power_in"))
      (node (ref "IC4") (pin "P9") (pinfunction "VSS_P9") (pintype "power_in"))
      (node (ref "IC5") (pin "A3") (pinfunction "VSS_A3") (pintype "power_in"))
      (node (ref "IC5") (pin "A7") (pinfunction "VSSQ_A7") (pintype "power_in"))
      (node (ref "IC5") (pin "B2") (pinfunction "VSSQ_B2") (pintype "power_in"))
      (node (ref "IC5") (pin "B8") (pinfunction "VSSQ_B8") (pintype "power_in"))
      (node (ref "IC5") (pin "D2") (pinfunction "VSSQ_D2") (pintype "power_in"))
      (node (ref "IC5") (pin "D8") (pinfunction "VSSQ_D8") (pintype "power_in"))
      (node (ref "IC5") (pin "E3") (pinfunction "VSS_E3") (pintype "power_in"))
      (node (ref "IC5") (pin "E7") (pinfunction "VSSQ_E7") (pintype "power_in"))
      (node (ref "IC5") (pin "F2") (pinfunction "VSSQ_F2") (pintype "power_in"))
      (node (ref "IC5") (pin "F8") (pinfunction "VSSQ_F8") (pintype "power_in"))
      (node (ref "IC5") (pin "H2") (pinfunction "VSSQ_H2") (pintype "power_in"))
      (node (ref "IC5") (pin "H8") (pinfunction "VSSQ_H8") (pintype "power_in"))
      (node (ref "IC5") (pin "J3") (pinfunction "VSS_J3") (pintype "power_in"))
      (node (ref "IC5") (pin "J7") (pinfunction "VSSDL_J7") (pintype "power_in"))
      (node (ref "IC5") (pin "N1") (pinfunction "VSS_N1") (pintype "power_in"))
      (node (ref "IC5") (pin "P9") (pinfunction "VSS_P9") (pintype "power_in"))
      (node (ref "R40") (pin "1") (pinfunction "1_1") (pintype "passive"))
      (node (ref "R41") (pin "1") (pinfunction "1_1") (pintype "passive"))
      (node (ref "R46") (pin "1") (pinfunction "1_1") (pintype "passive"))
      (node (ref "R47") (pin "1") (pinfunction "1_1") (pintype "passive"))
    )
    (net (code "105") (name "VCC1P8_DDR2") (class "Default")
      (node (ref "C100") (pin "2") (pinfunction "2_2") (pintype "passive"))
      (node (ref "C101") (pin "2") (pinfunction "2_2") (pintype "passive"))
      (node (ref "C102") (pin "2") (pinfunction "2_2") (pintype "passive"))
      (node (ref "C103") (pin "1") (pinfunction "1_1") (pintype "passive"))
      (node (ref "C105") (pin "2") (pinfunction "2_2") (pintype "passive"))
      (node (ref "C106") (pin "1") (pinfunction "1_1") (pintype "passive"))
      (node (ref "C107") (pin "1") (pinfunction "1_1") (pintype "passive"))
      (node (ref "C108") (pin "1") (pinfunction "1_1") (pintype "passive"))
      (node (ref "C109") (pin "1") (pinfunction "1_1") (pintype "passive"))
      (node (ref "C111") (pin "1") (pinfunction "1_1") (pintype "passive"))
      (node (ref "C112") (pin "1") (pinfunction "1_1") (pintype "passive"))
      (node (ref "C113") (pin "1") (pinfunction "1_1") (pintype "passive"))
      (node (ref "C114") (pin "1") (pinfunction "1_1") (pintype "passive"))
      (node (ref "C117") (pin "1") (pinfunction "1_1") (pintype "passive"))
      (node (ref "C118") (pin "1") (pinfunction "1_1") (pintype "passive"))
      (node (ref "C119") (pin "1") (pinfunction "1_1") (pintype "passive"))
      (node (ref "C120") (pin "1") (pinfunction "1_1") (pintype "passive"))
      (node (ref "C121") (pin "1") (pinfunction "1_1") (pintype "passive"))
      (node (ref "C122") (pin "1") (pinfunction "1_1") (pintype "passive"))
      (node (ref "C123") (pin "1") (pinfunction "1_1") (pintype "passive"))
      (node (ref "C124") (pin "1") (pinfunction "1_1") (pintype "passive"))
      (node (ref "C125") (pin "2") (pinfunction "2_2") (pintype "passive"))
      (node (ref "C126") (pin "2") (pinfunction "2_2") (pintype "passive"))
      (node (ref "C127") (pin "2") (pinfunction "2_2") (pintype "passive"))
      (node (ref "C128") (pin "1") (pinfunction "1_1") (pintype "passive"))
      (node (ref "C81") (pin "1") (pinfunction "1_1") (pintype "passive"))
      (node (ref "C82") (pin "1") (pinfunction "1_1") (pintype "passive"))
      (node (ref "C83") (pin "1") (pinfunction "1_1") (pintype "passive"))
      (node (ref "C84") (pin "1") (pinfunction "1_1") (pintype "passive"))
      (node (ref "C86") (pin "1") (pinfunction "1_1") (pintype "passive"))
      (node (ref "C87") (pin "1") (pinfunction "1_1") (pintype "passive"))
      (node (ref "C88") (pin "1") (pinfunction "1_1") (pintype "passive"))
      (node (ref "C89") (pin "1") (pinfunction "1_1") (pintype "passive"))
      (node (ref "C92") (pin "1") (pinfunction "1_1") (pintype "passive"))
      (node (ref "C93") (pin "1") (pinfunction "1_1") (pintype "passive"))
      (node (ref "C94") (pin "1") (pinfunction "1_1") (pintype "passive"))
      (node (ref "C95") (pin "1") (pinfunction "1_1") (pintype "passive"))
      (node (ref "C96") (pin "1") (pinfunction "1_1") (pintype "passive"))
      (node (ref "C97") (pin "1") (pinfunction "1_1") (pintype "passive"))
      (node (ref "C98") (pin "1") (pinfunction "1_1") (pintype "passive"))
      (node (ref "C99") (pin "1") (pinfunction "1_1") (pintype "passive"))
      (node (ref "IC4") (pin "A1") (pinfunction "VDD_A1") (pintype "power_in"))
      (node (ref "IC4") (pin "A9") (pinfunction "VDDQ_A9") (pintype "power_in"))
      (node (ref "IC4") (pin "C1") (pinfunction "VDDQ_C1") (pintype "power_in"))
      (node (ref "IC4") (pin "C3") (pinfunction "VDDQ_C3") (pintype "power_in"))
      (node (ref "IC4") (pin "C7") (pinfunction "VDDQ_C7") (pintype "power_in"))
      (node (ref "IC4") (pin "C9") (pinfunction "VDDQ_C9") (pintype "power_in"))
      (node (ref "IC4") (pin "E1") (pinfunction "VDD_E1") (pintype "power_in"))
      (node (ref "IC4") (pin "E9") (pinfunction "VDDQ_E9") (pintype "power_in"))
      (node (ref "IC4") (pin "G1") (pinfunction "VDDQ_G1") (pintype "power_in"))
      (node (ref "IC4") (pin "G3") (pinfunction "VDDQ_G3") (pintype "power_in"))
      (node (ref "IC4") (pin "G7") (pinfunction "VDDQ_G7") (pintype "power_in"))
      (node (ref "IC4") (pin "G9") (pinfunction "VDDQ_G9") (pintype "power_in"))
      (node (ref "IC4") (pin "J1") (pinfunction "VDDL_J1") (pintype "power_in"))
      (node (ref "IC4") (pin "J9") (pinfunction "VDD_J9") (pintype "power_in"))
      (node (ref "IC4") (pin "M9") (pinfunction "VDD_M9") (pintype "power_in"))
      (node (ref "IC4") (pin "R1") (pinfunction "VDD_R1") (pintype "power_in"))
      (node (ref "IC5") (pin "A1") (pinfunction "VDD_A1") (pintype "power_in"))
      (node (ref "IC5") (pin "A9") (pinfunction "VDDQ_A9") (pintype "power_in"))
      (node (ref "IC5") (pin "C1") (pinfunction "VDDQ_C1") (pintype "power_in"))
      (node (ref "IC5") (pin "C3") (pinfunction "VDDQ_C3") (pintype "power_in"))
      (node (ref "IC5") (pin "C7") (pinfunction "VDDQ_C7") (pintype "power_in"))
      (node (ref "IC5") (pin "C9") (pinfunction "VDDQ_C9") (pintype "power_in"))
      (node (ref "IC5") (pin "E1") (pinfunction "VDD_E1") (pintype "power_in"))
      (node (ref "IC5") (pin "E9") (pinfunction "VDDQ_E9") (pintype "power_in"))
      (node (ref "IC5") (pin "G1") (pinfunction "VDDQ_G1") (pintype "power_in"))
      (node (ref "IC5") (pin "G3") (pinfunction "VDDQ_G3") (pintype "power_in"))
      (node (ref "IC5") (pin "G7") (pinfunction "VDDQ_G7") (pintype "power_in"))
      (node (ref "IC5") (pin "G9") (pinfunction "VDDQ_G9") (pintype "power_in"))
      (node (ref "IC5") (pin "J1") (pinfunction "VDDL_J1") (pintype "power_in"))
      (node (ref "IC5") (pin "J9") (pinfunction "VDD_J9") (pintype "power_in"))
      (node (ref "IC5") (pin "M9") (pinfunction "VDD_M9") (pintype "power_in"))
      (node (ref "IC5") (pin "R1") (pinfunction "VDD_R1") (pintype "power_in"))
    )
    (net (code "106") (name "VTT_DDR2") (class "Default")
      (node (ref "C110") (pin "1") (pinfunction "1_1") (pintype "passive"))
      (node (ref "C110") (pin "2") (pinfunction "2_2") (pintype "passive"))
      (node (ref "C110") (pin "3") (pinfunction "3_3") (pintype "passive"))
      (node (ref "C110") (pin "4") (pinfunction "4_4") (pintype "passive"))
      (node (ref "C115") (pin "1") (pinfunction "1_1") (pintype "passive"))
      (node (ref "C115") (pin "2") (pinfunction "2_2") (pintype "passive"))
      (node (ref "C115") (pin "3") (pinfunction "3_3") (pintype "passive"))
      (node (ref "C115") (pin "4") (pinfunction "4_4") (pintype "passive"))
      (node (ref "C116") (pin "1") (pinfunction "1_1") (pintype "passive"))
      (node (ref "C116") (pin "2") (pinfunction "2_2") (pintype "passive"))
      (node (ref "C116") (pin "3") (pinfunction "3_3") (pintype "passive"))
      (node (ref "C116") (pin "4") (pinfunction "4_4") (pintype "passive"))
      (node (ref "C85") (pin "1") (pinfunction "1_1") (pintype "passive"))
      (node (ref "C85") (pin "2") (pinfunction "2_2") (pintype "passive"))
      (node (ref "C85") (pin "3") (pinfunction "3_3") (pintype "passive"))
      (node (ref "C85") (pin "4") (pinfunction "4_4") (pintype "passive"))
      (node (ref "C90") (pin "1") (pinfunction "1_1") (pintype "passive"))
      (node (ref "C90") (pin "2") (pinfunction "2_2") (pintype "passive"))
      (node (ref "C90") (pin "3") (pinfunction "3_3") (pintype "passive"))
      (node (ref "C90") (pin "4") (pinfunction "4_4") (pintype "passive"))
      (node (ref "C91") (pin "1") (pinfunction "1_1") (pintype "passive"))
      (node (ref "C91") (pin "2") (pinfunction "2_2") (pintype "passive"))
      (node (ref "C91") (pin "3") (pinfunction "3_3") (pintype "passive"))
      (node (ref "C91") (pin "4") (pinfunction "4_4") (pintype "passive"))
      (node (ref "R36") (pin "10") (pinfunction "10_10") (pintype "passive"))
      (node (ref "R36") (pin "11") (pinfunction "11_11") (pintype "passive"))
      (node (ref "R36") (pin "12") (pinfunction "12_12") (pintype "passive"))
      (node (ref "R36") (pin "13") (pinfunction "13_13") (pintype "passive"))
      (node (ref "R36") (pin "14") (pinfunction "14_14") (pintype "passive"))
      (node (ref "R36") (pin "15") (pinfunction "15_15") (pintype "passive"))
      (node (ref "R36") (pin "16") (pinfunction "16_16") (pintype "passive"))
      (node (ref "R36") (pin "9") (pinfunction "9_9") (pintype "passive"))
      (node (ref "R38") (pin "10") (pinfunction "10_10") (pintype "passive"))
      (node (ref "R38") (pin "11") (pinfunction "11_11") (pintype "passive"))
      (node (ref "R38") (pin "12") (pinfunction "12_12") (pintype "passive"))
      (node (ref "R38") (pin "13") (pinfunction "13_13") (pintype "passive"))
      (node (ref "R38") (pin "14") (pinfunction "14_14") (pintype "passive"))
      (node (ref "R38") (pin "15") (pinfunction "15_15") (pintype "passive"))
      (node (ref "R38") (pin "16") (pinfunction "16_16") (pintype "passive"))
      (node (ref "R38") (pin "9") (pinfunction "9_9") (pintype "passive"))
      (node (ref "R39") (pin "10") (pinfunction "10_10") (pintype "passive"))
      (node (ref "R39") (pin "11") (pinfunction "11_11") (pintype "passive"))
      (node (ref "R39") (pin "12") (pinfunction "12_12") (pintype "passive"))
      (node (ref "R39") (pin "13") (pinfunction "13_13") (pintype "passive"))
      (node (ref "R39") (pin "14") (pinfunction "14_14") (pintype "passive"))
      (node (ref "R39") (pin "15") (pinfunction "15_15") (pintype "passive"))
      (node (ref "R39") (pin "16") (pinfunction "16_16") (pintype "passive"))
      (node (ref "R39") (pin "9") (pinfunction "9_9") (pintype "passive"))
      (node (ref "R42") (pin "10") (pinfunction "10_10") (pintype "passive"))
      (node (ref "R42") (pin "11") (pinfunction "11_11") (pintype "passive"))
      (node (ref "R42") (pin "12") (pinfunction "12_12") (pintype "passive"))
      (node (ref "R42") (pin "13") (pinfunction "13_13") (pintype "passive"))
      (node (ref "R42") (pin "14") (pinfunction "14_14") (pintype "passive"))
      (node (ref "R42") (pin "15") (pinfunction "15_15") (pintype "passive"))
      (node (ref "R42") (pin "16") (pinfunction "16_16") (pintype "passive"))
      (node (ref "R42") (pin "9") (pinfunction "9_9") (pintype "passive"))
      (node (ref "R44") (pin "10") (pinfunction "10_10") (pintype "passive"))
      (node (ref "R44") (pin "11") (pinfunction "11_11") (pintype "passive"))
      (node (ref "R44") (pin "12") (pinfunction "12_12") (pintype "passive"))
      (node (ref "R44") (pin "13") (pinfunction "13_13") (pintype "passive"))
      (node (ref "R44") (pin "14") (pinfunction "14_14") (pintype "passive"))
      (node (ref "R44") (pin "15") (pinfunction "15_15") (pintype "passive"))
      (node (ref "R44") (pin "16") (pinfunction "16_16") (pintype "passive"))
      (node (ref "R44") (pin "9") (pinfunction "9_9") (pintype "passive"))
      (node (ref "R45") (pin "10") (pinfunction "10_10") (pintype "passive"))
      (node (ref "R45") (pin "11") (pinfunction "11_11") (pintype "passive"))
      (node (ref "R45") (pin "12") (pinfunction "12_12") (pintype "passive"))
      (node (ref "R45") (pin "13") (pinfunction "13_13") (pintype "passive"))
      (node (ref "R45") (pin "14") (pinfunction "14_14") (pintype "passive"))
      (node (ref "R45") (pin "15") (pinfunction "15_15") (pintype "passive"))
      (node (ref "R45") (pin "16") (pinfunction "16_16") (pintype "passive"))
      (node (ref "R45") (pin "9") (pinfunction "9_9") (pintype "passive"))
    )
    (net (code "107") (name "unconnected-(IC4B-NC-PadA2)") (class "Default")
      (node (ref "IC4") (pin "A2") (pinfunction "NC_A2") (pintype "passive+no_connect"))
    )
    (net (code "108") (name "unconnected-(IC4B-NC-PadE2)") (class "Default")
      (node (ref "IC4") (pin "E2") (pinfunction "NC_E2") (pintype "passive+no_connect"))
    )
    (net (code "109") (name "unconnected-(IC4B-NC-PadR3)") (class "Default")
      (node (ref "IC4") (pin "R3") (pinfunction "NC_R3") (pintype "passive+no_connect"))
    )
    (net (code "110") (name "unconnected-(IC4B-NC-PadR7)") (class "Default")
      (node (ref "IC4") (pin "R7") (pinfunction "NC_R7") (pintype "passive+no_connect"))
    )
    (net (code "111") (name "unconnected-(IC4B-NC-PadR8)") (class "Default")
      (node (ref "IC4") (pin "R8") (pinfunction "NC_R8") (pintype "passive+no_connect"))
    )
    (net (code "112") (name "unconnected-(IC5B-NC-PadA2)") (class "Default")
      (node (ref "IC5") (pin "A2") (pinfunction "NC_A2") (pintype "passive+no_connect"))
    )
    (net (code "113") (name "unconnected-(IC5B-NC-PadE2)") (class "Default")
      (node (ref "IC5") (pin "E2") (pinfunction "NC_E2") (pintype "passive+no_connect"))
    )
    (net (code "114") (name "unconnected-(IC5B-NC-PadR3)") (class "Default")
      (node (ref "IC5") (pin "R3") (pinfunction "NC_R3") (pintype "passive+no_connect"))
    )
    (net (code "115") (name "unconnected-(IC5B-NC-PadR7)") (class "Default")
      (node (ref "IC5") (pin "R7") (pinfunction "NC_R7") (pintype "passive+no_connect"))
    )
    (net (code "116") (name "unconnected-(IC5B-NC-PadR8)") (class "Default")
      (node (ref "IC5") (pin "R8") (pinfunction "NC_R8") (pintype "passive+no_connect"))
    )
    (net (code "117") (name "unconnected-(R39-Pad7)") (class "Default")
      (node (ref "R39") (pin "7") (pinfunction "7_7") (pintype "passive+no_connect"))
    )
    (net (code "118") (name "unconnected-(R39-Pad8)") (class "Default")
      (node (ref "R39") (pin "8") (pinfunction "8_8") (pintype "passive+no_connect"))
    )
    (net (code "119") (name "unconnected-(R45-Pad1)") (class "Default")
      (node (ref "R45") (pin "1") (pinfunction "1_1") (pintype "passive+no_connect"))
    )
    (net (code "120") (name "unconnected-(R45-Pad7)") (class "Default")
      (node (ref "R45") (pin "7") (pinfunction "7_7") (pintype "passive+no_connect"))
    )
  )
)
